# power.net
KiCad netlist of a schematic drawn in Altium Designer
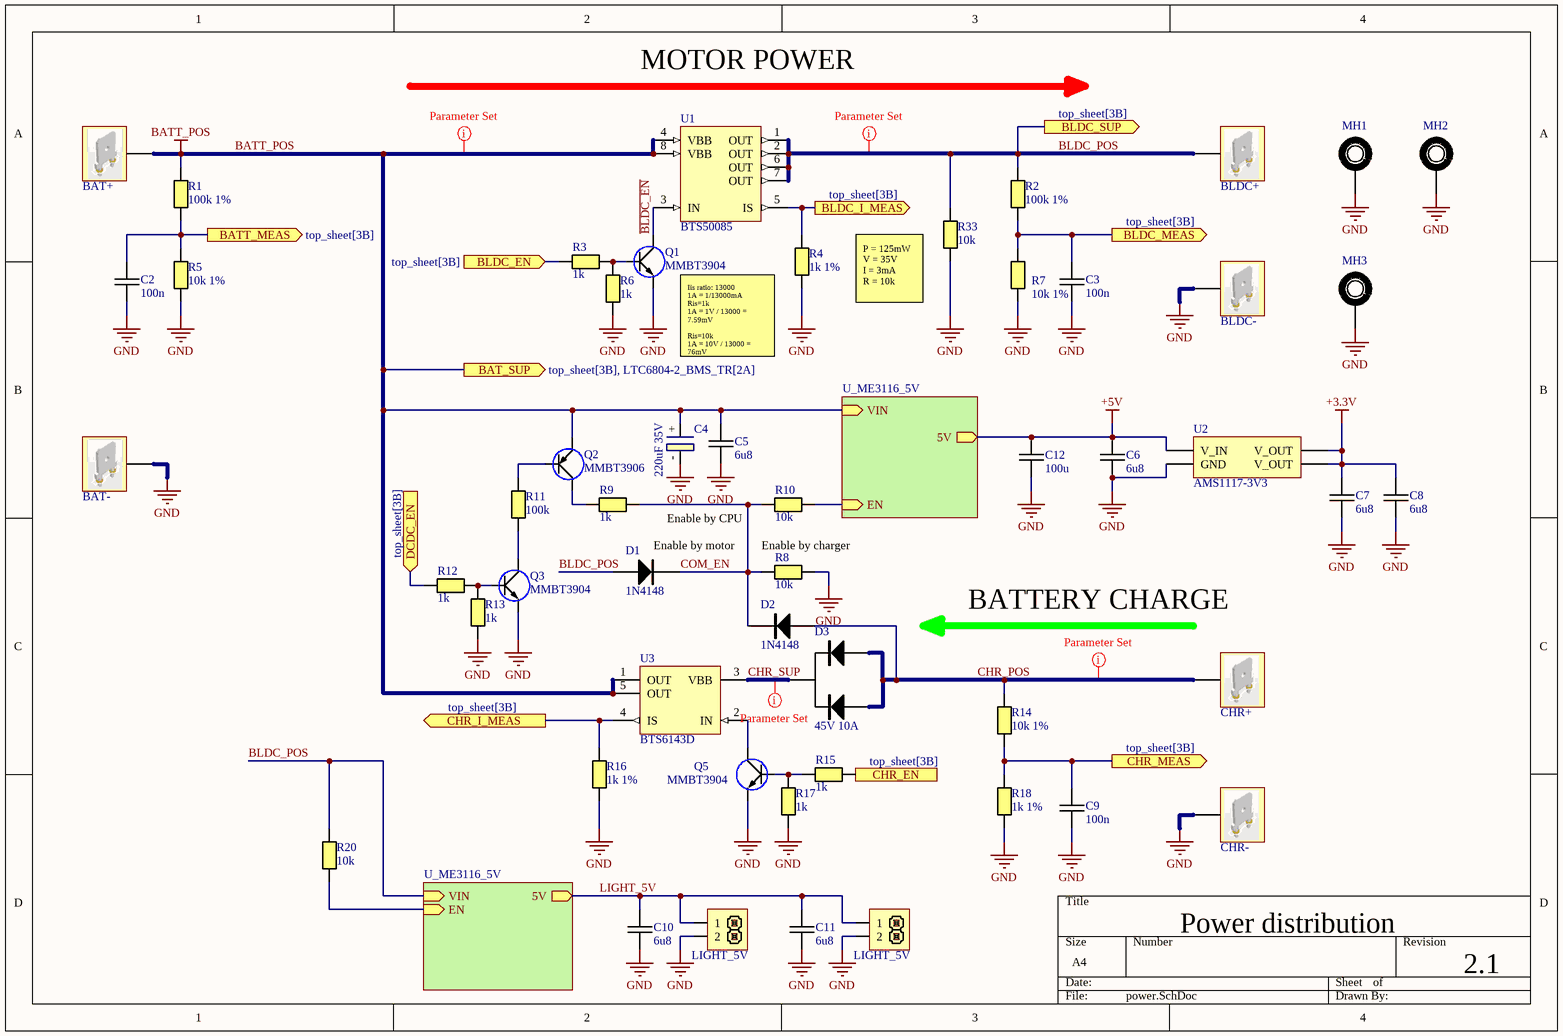
[diagram p0: power.SchDoc]

(export (version "E")
  (design (tool "Eeschema 10.0.6"))
  (components
    (comp (ref "BAT+")
      (value "Crimp 6.3 single PCB")
      (footprint "Crimp 6.3mm single PCB")
      (description "Straight Mount Angle PCB Tab Terminal")
      (libsource (lib "Connectors") (part "Crimp 6.3 single PCB"))
    )
    (comp (ref "BAT-")
      (value "Crimp 6.3 single PCB")
      (footprint "Crimp 6.3mm single PCB")
      (description "Straight Mount Angle PCB Tab Terminal")
      (libsource (lib "Connectors") (part "Crimp 6.3 single PCB"))
    )
    (comp (ref "BLDC+")
      (value "Crimp 6.3 single PCB")
      (footprint "Crimp 6.3mm single PCB")
      (description "Straight Mount Angle PCB Tab Terminal")
      (libsource (lib "") (part "Crimp 6.3 single PCB_1"))
    )
    (comp (ref "BLDC-")
      (value "Crimp 6.3 single PCB")
      (footprint "Crimp 6.3mm single PCB")
      (description "Straight Mount Angle PCB Tab Terminal")
      (libsource (lib "") (part "Crimp 6.3 single PCB_1"))
    )
    (comp (ref "C2")
      (value "100n")
      (footprint "CAPC0603(1608)55_N")
      (description "Ceramic capacitor Medium density")
      (libsource (lib "Discrete") (part "Capacitor M"))
    )
    (comp (ref "C3")
      (value "100n")
      (footprint "CAPC0603(1608)55_N")
      (description "Ceramic capacitor Medium density")
      (libsource (lib "Discrete") (part "Capacitor M"))
    )
    (comp (ref "C4")
      (value "220uF 35V")
      (footprint "10x10.5 Capacitor")
      (description "Capacitor Electrolitic")
      (libsource (lib "Discrete") (part "Capacitor Electrolitic"))
    )
    (comp (ref "C5")
      (value "6u8")
      (footprint "CAPC0805(2012)75_N")
      (description "Ceramic capacitor Medium density")
      (libsource (lib "Discrete") (part "Capacitor M"))
    )
    (comp (ref "C6")
      (value "6u8")
      (footprint "CAPC0805(2012)75_N")
      (description "Ceramic capacitor Medium density")
      (libsource (lib "Discrete") (part "Capacitor M"))
    )
    (comp (ref "C7")
      (value "6u8")
      (footprint "CAPC0805(2012)75_N")
      (description "Ceramic capacitor Medium density")
      (libsource (lib "Discrete") (part "Capacitor M"))
    )
    (comp (ref "C8")
      (value "6u8")
      (footprint "CAPC0805(2012)75_N")
      (description "Ceramic capacitor Medium density")
      (libsource (lib "Discrete") (part "Capacitor M"))
    )
    (comp (ref "C9")
      (value "100n")
      (footprint "CAPC0603(1608)55_N")
      (description "Ceramic capacitor Medium density")
      (libsource (lib "Discrete") (part "Capacitor M"))
    )
    (comp (ref "C10")
      (value "6u8")
      (footprint "CAPC0805(2012)75_N")
      (description "Ceramic capacitor Medium density")
      (libsource (lib "Discrete") (part "Capacitor M"))
    )
    (comp (ref "C11")
      (value "6u8")
      (footprint "CAPC0805(2012)75_N")
      (description "Ceramic capacitor Medium density")
      (libsource (lib "Discrete") (part "Capacitor M"))
    )
    (comp (ref "C12")
      (value "100u")
      (footprint "CAPC1206(3216)75_N")
      (description "Ceramic capacitor Medium density")
      (libsource (lib "Discrete") (part "Capacitor M"))
    )
    (comp (ref "CHR+")
      (value "Crimp 6.3 single PCB")
      (footprint "Crimp 6.3mm single PCB")
      (description "Straight Mount Angle PCB Tab Terminal")
      (libsource (lib "") (part "Crimp 6.3 single PCB_1"))
    )
    (comp (ref "CHR-")
      (value "Crimp 6.3 single PCB")
      (footprint "Crimp 6.3mm single PCB")
      (description "Straight Mount Angle PCB Tab Terminal")
      (libsource (lib "") (part "Crimp 6.3 single PCB_1"))
    )
    (comp (ref "CN1")
      (value "PIN HEADER 1x2")
      (footprint "XH2.54 2P")
      (description "LIGHT_5V")
      (fields (field (name "PARAMETER 1") "LIGHT_5V"))
      (libsource (lib "Connectors") (part "PIN HEADER 2.54 1x2"))
    )
    (comp (ref "CN2")
      (value "PIN HEADER 1x2")
      (footprint "XH2.54 2P")
      (description "LIGHT_5V")
      (fields (field (name "PARAMETER 1") "LIGHT_5V"))
      (libsource (lib "Connectors") (part "PIN HEADER 2.54 1x2"))
    )
    (comp (ref "D1")
      (value "1N4148")
      (footprint "SOD80")
      (description "Small Signal Fast Switching Diodes")
      (libsource (lib "Diodes") (part "1N4148"))
    )
    (comp (ref "D2")
      (value "1N4148")
      (footprint "SOD80")
      (description "Small Signal Fast Switching Diodes")
      (libsource (lib "Diodes") (part "1N4148"))
    )
    (comp (ref "D3")
      (value "45V 10A")
      (footprint "DPAK")
      (description "Power schottky rectifier")
      (libsource (lib "Diodes") (part "STPS1045B"))
    )
    (comp (ref "MH1")
      (value "Mounting Hole")
      (footprint "MH_M3")
      (libsource (lib "Connectors") (part "Mounting Hole"))
    )
    (comp (ref "MH2")
      (value "Mounting Hole")
      (footprint "MH_M3")
      (libsource (lib "Connectors") (part "Mounting Hole"))
    )
    (comp (ref "MH3")
      (value "Mounting Hole")
      (footprint "MH_M3")
      (libsource (lib "Connectors") (part "Mounting Hole"))
    )
    (comp (ref "Q1")
      (value "MMBT3904")
      (footprint "SOT23")
      (description "NPN General Purpose Transistor")
      (libsource (lib "Transistors") (part "2N3904"))
    )
    (comp (ref "Q2")
      (value "MMBT3906")
      (footprint "SOT23")
      (description "PNP General Purpose Transistor")
      (libsource (lib "Transistors") (part "2N3906"))
    )
    (comp (ref "Q3")
      (value "MMBT3904")
      (footprint "SOT23")
      (description "NPN General Purpose Transistor")
      (libsource (lib "Transistors") (part "2N3904"))
    )
    (comp (ref "Q5")
      (value "MMBT3904")
      (footprint "SOT23")
      (description "NPN General Purpose Transistor")
      (libsource (lib "Transistors") (part "2N3904"))
    )
    (comp (ref "R1")
      (value "100k 1%")
      (footprint "RESC0603(1608)_N")
      (description "Resistor Medium Density")
      (libsource (lib "Discrete") (part "Resistor M"))
    )
    (comp (ref "R2")
      (value "100k 1%")
      (footprint "RESC0603(1608)_N")
      (description "Resistor Medium Density")
      (libsource (lib "Discrete") (part "Resistor M"))
    )
    (comp (ref "R3")
      (value "1k")
      (footprint "RESC0603(1608)_N")
      (description "Resistor Medium Density")
      (libsource (lib "") (part "Resistor M_1"))
    )
    (comp (ref "R4")
      (value "1k 1%")
      (footprint "RESC0603(1608)_N")
      (description "Resistor Medium Density")
      (libsource (lib "Discrete") (part "Resistor M"))
    )
    (comp (ref "R5")
      (value "10k 1%")
      (footprint "RESC0603(1608)_N")
      (description "Resistor Medium Density")
      (libsource (lib "Discrete") (part "Resistor M"))
    )
    (comp (ref "R6")
      (value "1k")
      (footprint "RESC0603(1608)_N")
      (description "Resistor Medium Density")
      (libsource (lib "Discrete") (part "Resistor M"))
    )
    (comp (ref "R7")
      (value "10k 1%")
      (footprint "RESC0603(1608)_N")
      (description "Resistor Medium Density")
      (libsource (lib "Discrete") (part "Resistor M"))
    )
    (comp (ref "R8")
      (value "10k")
      (footprint "RESC0603(1608)_N")
      (description "Resistor Medium Density")
      (libsource (lib "") (part "Resistor M_1"))
    )
    (comp (ref "R9")
      (value "1k")
      (footprint "RESC0603(1608)_N")
      (description "Resistor Medium Density")
      (libsource (lib "") (part "Resistor M_2"))
    )
    (comp (ref "R10")
      (value "10k")
      (footprint "RESC0603(1608)_N")
      (description "Resistor Medium Density")
      (libsource (lib "") (part "Resistor M_2"))
    )
    (comp (ref "R11")
      (value "100k")
      (footprint "RESC0603(1608)_N")
      (description "Resistor Medium Density")
      (libsource (lib "") (part "Resistor M_3"))
    )
    (comp (ref "R12")
      (value "1k")
      (footprint "RESC0603(1608)_N")
      (description "Resistor Medium Density")
      (libsource (lib "") (part "Resistor M_1"))
    )
    (comp (ref "R13")
      (value "1k")
      (footprint "RESC0603(1608)_N")
      (description "Resistor Medium Density")
      (libsource (lib "Discrete") (part "Resistor M"))
    )
    (comp (ref "R14")
      (value "10k 1%")
      (footprint "RESC0603(1608)_N")
      (description "Resistor Medium Density")
      (libsource (lib "Discrete") (part "Resistor M"))
    )
    (comp (ref "R15")
      (value "1k")
      (footprint "RESC0603(1608)_N")
      (description "Resistor Medium Density")
      (libsource (lib "") (part "Resistor M_3"))
    )
    (comp (ref "R16")
      (value "1k 1%")
      (footprint "RESC0603(1608)_N")
      (description "Resistor Medium Density")
      (libsource (lib "Discrete") (part "Resistor M"))
    )
    (comp (ref "R17")
      (value "1k")
      (footprint "RESC0603(1608)_N")
      (description "Resistor Medium Density")
      (libsource (lib "Discrete") (part "Resistor M"))
    )
    (comp (ref "R18")
      (value "1k 1%")
      (footprint "RESC0603(1608)_N")
      (description "Resistor Medium Density")
      (libsource (lib "Discrete") (part "Resistor M"))
    )
    (comp (ref "R20")
      (value "10k")
      (footprint "RESC0603(1608)_N")
      (description "Resistor Medium Density")
      (libsource (lib "Discrete") (part "Resistor M"))
    )
    (comp (ref "R33")
      (value "10k")
      (footprint "RESC0805(2012)_N")
      (description "Resistor Medium Density")
      (libsource (lib "Discrete") (part "Resistor M"))
    )
    (comp (ref "U1")
      (value "BTS50085")
      (footprint "PG-TO220-7-4")
      (description "Smart Highside High Current Power Switch")
      (libsource (lib "Switches") (part "BTS50085-1TMA"))
    )
    (comp (ref "U2")
      (value "AMS1117-3V3")
      (footprint "SOT229P700X180-4N")
      (description "800mA LDO  15V max")
      (libsource (lib "VoltageRegulators") (part "AMS1117"))
    )
    (comp (ref "U3")
      (value "BTS6143D")
      (footprint "ITO252-5-11_M")
      (fields (field (name "MANUFACTURER") "Infineon"))
      (libsource (lib "Switches") (part "BTS6143D"))
    )
  )
  (nets
    (net (code "1") (name "+3.3V") (class "Default")
      (node (ref "C7") (pin "1") (pinfunction "1_1") (pintype "passive"))
      (node (ref "C8") (pin "1") (pinfunction "1_1") (pintype "passive"))
      (node (ref "U2") (pin "2") (pinfunction "V_OUT_2") (pintype "passive"))
      (node (ref "U2") (pin "4") (pinfunction "V_OUT_4") (pintype "passive"))
    )
    (net (code "2") (name "+5V") (class "Default")
      (node (ref "C12") (pin "1") (pinfunction "1_1") (pintype "passive"))
      (node (ref "C6") (pin "1") (pinfunction "1_1") (pintype "passive"))
      (node (ref "U2") (pin "3") (pinfunction "V_IN_3") (pintype "passive"))
    )
    (net (code "3") (name "/BATT_MEAS") (class "Default")
      (node (ref "C2") (pin "1") (pinfunction "1_1") (pintype "passive"))
      (node (ref "R1") (pin "1") (pinfunction "1_1") (pintype "passive"))
      (node (ref "R5") (pin "2") (pinfunction "2_2") (pintype "passive"))
    )
    (net (code "4") (name "/BLDC_EN") (class "Default")
      (node (ref "R3") (pin "1") (pinfunction "1_1") (pintype "passive"))
    )
    (net (code "5") (name "/BLDC_I_MEAS") (class "Default")
      (node (ref "R4") (pin "2") (pinfunction "2_2") (pintype "passive"))
      (node (ref "U1") (pin "5") (pinfunction "IS_5") (pintype "output"))
    )
    (net (code "6") (name "/BLDC_MEAS") (class "Default")
      (node (ref "C3") (pin "1") (pinfunction "1_1") (pintype "passive"))
      (node (ref "R2") (pin "1") (pinfunction "1_1") (pintype "passive"))
      (node (ref "R7") (pin "2") (pinfunction "2_2") (pintype "passive"))
    )
    (net (code "7") (name "/BLDC_POS") (class "Default")
      (node (ref "BLDC+") (pin "1") (pintype "passive"))
      (node (ref "D1") (pin "1") (pinfunction "A_1") (pintype "passive"))
      (node (ref "R2") (pin "2") (pinfunction "2_2") (pintype "passive"))
      (node (ref "R20") (pin "2") (pinfunction "2_2") (pintype "passive"))
      (node (ref "R33") (pin "2") (pinfunction "2_2") (pintype "passive"))
      (node (ref "U1") (pin "1") (pinfunction "OUT_1") (pintype "output"))
      (node (ref "U1") (pin "2") (pinfunction "OUT_2") (pintype "output"))
      (node (ref "U1") (pin "6") (pinfunction "OUT_6") (pintype "output"))
      (node (ref "U1") (pin "7") (pinfunction "OUT_7") (pintype "output"))
    )
    (net (code "8") (name "/CHR_EN") (class "Default")
      (node (ref "R15") (pin "1") (pinfunction "1_1") (pintype "passive"))
    )
    (net (code "9") (name "/CHR_I_MEAS") (class "Default")
      (node (ref "R16") (pin "2") (pinfunction "2_2") (pintype "passive"))
      (node (ref "U3") (pin "4") (pinfunction "IS_4") (pintype "output"))
    )
    (net (code "10") (name "/CHR_MEAS") (class "Default")
      (node (ref "C9") (pin "1") (pinfunction "1_1") (pintype "passive"))
      (node (ref "R14") (pin "1") (pinfunction "1_1") (pintype "passive"))
      (node (ref "R18") (pin "2") (pinfunction "2_2") (pintype "passive"))
    )
    (net (code "11") (name "/CHR_POS") (class "Default")
      (node (ref "CHR+") (pin "1") (pintype "passive"))
      (node (ref "D2") (pin "1") (pinfunction "A_1") (pintype "passive"))
      (node (ref "D3") (pin "1") (pinfunction "A1_1") (pintype "passive"))
      (node (ref "D3") (pin "3") (pinfunction "A2_3") (pintype "passive"))
      (node (ref "R14") (pin "2") (pinfunction "2_2") (pintype "passive"))
    )
    (net (code "12") (name "/CHR_SUP") (class "Default")
      (node (ref "D3") (pin "2") (pinfunction "K_2") (pintype "passive"))
      (node (ref "U3") (pin "3") (pinfunction "VBB_3") (pintype "power_in"))
    )
    (net (code "13") (name "/COM_EN") (class "Default")
      (node (ref "D1") (pin "2") (pinfunction "K_2") (pintype "passive"))
      (node (ref "D2") (pin "2") (pinfunction "K_2") (pintype "passive"))
      (node (ref "R10") (pin "2") (pinfunction "2_2") (pintype "passive"))
      (node (ref "R8") (pin "1") (pinfunction "1_1") (pintype "passive"))
      (node (ref "R9") (pin "1") (pinfunction "1_1") (pintype "passive"))
    )
    (net (code "14") (name "/DCDC_EN") (class "Default")
      (node (ref "R12") (pin "1") (pinfunction "1_1") (pintype "passive"))
    )
    (net (code "15") (name "/EN") (class "Default")
      (node (ref "R20") (pin "1") (pinfunction "1_1") (pintype "passive"))
    )
    (net (code "16") (name "/EN_1") (class "Default")
      (node (ref "R10") (pin "1") (pinfunction "1_1") (pintype "passive"))
    )
    (net (code "17") (name "/LIGHT_5V") (class "Default")
      (node (ref "C10") (pin "1") (pinfunction "1_1") (pintype "passive"))
      (node (ref "C11") (pin "1") (pinfunction "1_1") (pintype "passive"))
      (node (ref "CN1") (pin "1") (pinfunction "1_1") (pintype "passive"))
      (node (ref "CN2") (pin "1") (pinfunction "1_1") (pintype "passive"))
    )
    (net (code "18") (name "/~{BLDC_EN}") (class "Default")
      (node (ref "Q1") (pin "3") (pinfunction "C_3") (pintype "passive"))
      (node (ref "U1") (pin "3") (pinfunction "IN_3") (pintype "input"))
    )
    (net (code "19") (name "BATT_POS") (class "Default")
      (node (ref "BAT+") (pin "1") (pintype "passive"))
      (node (ref "C4") (pin "+") (pinfunction "+_+") (pintype "passive"))
      (node (ref "C5") (pin "2") (pinfunction "2_2") (pintype "passive"))
      (node (ref "Q2") (pin "2") (pinfunction "E_2") (pintype "passive"))
      (node (ref "R1") (pin "2") (pinfunction "2_2") (pintype "passive"))
      (node (ref "U1") (pin "4") (pinfunction "VBB_4") (pintype "input"))
      (node (ref "U1") (pin "8") (pinfunction "VBB_8") (pintype "input"))
      (node (ref "U3") (pin "1") (pinfunction "OUT_1") (pintype "tri_state"))
      (node (ref "U3") (pin "5") (pinfunction "OUT_5") (pintype "tri_state"))
    )
    (net (code "20") (name "GND") (class "Default")
      (node (ref "BAT-") (pin "1") (pintype "passive"))
      (node (ref "BLDC-") (pin "1") (pintype "passive"))
      (node (ref "C10") (pin "2") (pinfunction "2_2") (pintype "passive"))
      (node (ref "C11") (pin "2") (pinfunction "2_2") (pintype "passive"))
      (node (ref "C12") (pin "2") (pinfunction "2_2") (pintype "passive"))
      (node (ref "C2") (pin "2") (pinfunction "2_2") (pintype "passive"))
      (node (ref "C3") (pin "2") (pinfunction "2_2") (pintype "passive"))
      (node (ref "C4") (pin "-") (pinfunction "-_-") (pintype "passive"))
      (node (ref "C5") (pin "1") (pinfunction "1_1") (pintype "passive"))
      (node (ref "C6") (pin "2") (pinfunction "2_2") (pintype "passive"))
      (node (ref "C7") (pin "2") (pinfunction "2_2") (pintype "passive"))
      (node (ref "C8") (pin "2") (pinfunction "2_2") (pintype "passive"))
      (node (ref "C9") (pin "2") (pinfunction "2_2") (pintype "passive"))
      (node (ref "CHR-") (pin "1") (pintype "passive"))
      (node (ref "CN1") (pin "2") (pinfunction "2_2") (pintype "passive"))
      (node (ref "CN2") (pin "2") (pinfunction "2_2") (pintype "passive"))
      (node (ref "MH1") (pin "1") (pintype "passive"))
      (node (ref "MH2") (pin "1") (pintype "passive"))
      (node (ref "MH3") (pin "1") (pintype "passive"))
      (node (ref "Q1") (pin "2") (pinfunction "E_2") (pintype "passive"))
      (node (ref "Q3") (pin "2") (pinfunction "E_2") (pintype "passive"))
      (node (ref "Q5") (pin "2") (pinfunction "E_2") (pintype "passive"))
      (node (ref "R13") (pin "1") (pinfunction "1_1") (pintype "passive"))
      (node (ref "R16") (pin "1") (pinfunction "1_1") (pintype "passive"))
      (node (ref "R17") (pin "1") (pinfunction "1_1") (pintype "passive"))
      (node (ref "R18") (pin "1") (pinfunction "1_1") (pintype "passive"))
      (node (ref "R33") (pin "1") (pinfunction "1_1") (pintype "passive"))
      (node (ref "R4") (pin "1") (pinfunction "1_1") (pintype "passive"))
      (node (ref "R5") (pin "1") (pinfunction "1_1") (pintype "passive"))
      (node (ref "R6") (pin "1") (pinfunction "1_1") (pintype "passive"))
      (node (ref "R7") (pin "1") (pinfunction "1_1") (pintype "passive"))
      (node (ref "R8") (pin "2") (pinfunction "2_2") (pintype "passive"))
      (node (ref "U2") (pin "1") (pinfunction "GND_1") (pintype "passive"))
    )
    (net (code "21") (name "Net-(Q1-B)") (class "Default")
      (node (ref "Q1") (pin "1") (pinfunction "B_1") (pintype "passive"))
      (node (ref "R3") (pin "2") (pinfunction "2_2") (pintype "passive"))
      (node (ref "R6") (pin "2") (pinfunction "2_2") (pintype "passive"))
    )
    (net (code "22") (name "Net-(Q2-B)") (class "Default")
      (node (ref "Q2") (pin "1") (pinfunction "B_1") (pintype "passive"))
      (node (ref "R11") (pin "1") (pinfunction "1_1") (pintype "passive"))
    )
    (net (code "23") (name "Net-(Q2-C)") (class "Default")
      (node (ref "Q2") (pin "3") (pinfunction "C_3") (pintype "passive"))
      (node (ref "R9") (pin "2") (pinfunction "2_2") (pintype "passive"))
    )
    (net (code "24") (name "Net-(Q3-B)") (class "Default")
      (node (ref "Q3") (pin "1") (pinfunction "B_1") (pintype "passive"))
      (node (ref "R12") (pin "2") (pinfunction "2_2") (pintype "passive"))
      (node (ref "R13") (pin "2") (pinfunction "2_2") (pintype "passive"))
    )
    (net (code "25") (name "Net-(Q3-C)") (class "Default")
      (node (ref "Q3") (pin "3") (pinfunction "C_3") (pintype "passive"))
      (node (ref "R11") (pin "2") (pinfunction "2_2") (pintype "passive"))
    )
    (net (code "26") (name "Net-(Q5-B)") (class "Default")
      (node (ref "Q5") (pin "1") (pinfunction "B_1") (pintype "passive"))
      (node (ref "R15") (pin "2") (pinfunction "2_2") (pintype "passive"))
      (node (ref "R17") (pin "2") (pinfunction "2_2") (pintype "passive"))
    )
    (net (code "27") (name "Net-(Q5-C)") (class "Default")
      (node (ref "Q5") (pin "3") (pinfunction "C_3") (pintype "passive"))
      (node (ref "U3") (pin "2") (pinfunction "IN_2") (pintype "input"))
    )
  )
)
